# design.net
KiCad netlist of a schematic drawn in Altium Designer
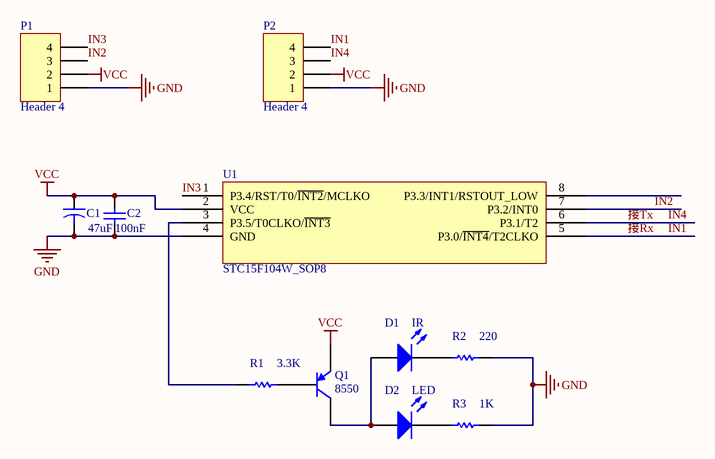
[diagram p0: 红外发射.SchDoc]

(export (version "E")
  (design (tool "Eeschema 10.0.6"))
  (components
    (comp (ref "C1")
      (value "47uF")
      (footprint "C1210_L")
      (description "Capacitor")
      (fields (field (name "Comment") "Cap2") (field (name "PUBLISHER") "Altium Limited"))
      (libsource (lib "Miscellaneous Devices") (part "Cap2"))
    )
    (comp (ref "C2")
      (value "100nF")
      (footprint "6-0805_N")
      (description "Capacitor")
      (fields (field (name "Comment") "Cap") (field (name "PUBLISHER") "Altium Limited"))
      (libsource (lib "Miscellaneous Devices") (part "Cap"))
    )
    (comp (ref "D1")
      (value "IR")
      (footprint "PIN2")
      (description "Typical INFRARED GaAs LED")
      (fields (field (name "PUBLISHER") "Altium Limited"))
      (libsource (lib "Miscellaneous Devices") (part "LED0"))
    )
    (comp (ref "D2")
      (value "LED")
      (footprint "6-0805_N")
      (description "Typical INFRARED GaAs LED")
      (fields (field (name "PUBLISHER") "Altium Limited"))
      (libsource (lib "Miscellaneous Devices") (part "LED0"))
    )
    (comp (ref "P1")
      (value "Header 4")
      (footprint "HDR1X4")
      (description "Header, 4-Pin")
      (fields (field (name "PUBLISHER") "Altium Limited"))
      (libsource (lib "Miscellaneous Connectors") (part "Header 4"))
    )
    (comp (ref "P2")
      (value "Header 4")
      (footprint "HDR1X4")
      (description "Header, 4-Pin")
      (fields (field (name "PUBLISHER") "Altium Limited"))
      (libsource (lib "Miscellaneous Connectors") (part "Header 4"))
    )
    (comp (ref "Q1")
      (value "8550")
      (footprint "SOT-23_N")
      (description "PNP General Purpose Amplifier")
      (fields (field (name "PUBLISHER") "Altium Limited"))
      (libsource (lib "Miscellaneous Devices") (part "2N3906"))
    )
    (comp (ref "R1")
      (value "3.3K")
      (footprint "6-0805_N")
      (description "Resistor")
      (fields (field (name "Comment") "Res1") (field (name "PUBLISHER") "Altium Limited"))
      (libsource (lib "Miscellaneous Devices") (part "Res1"))
    )
    (comp (ref "R2")
      (value "220")
      (footprint "6-0805_N")
      (description "Resistor")
      (fields (field (name "Comment") "Res1") (field (name "PUBLISHER") "Altium Limited"))
      (libsource (lib "Miscellaneous Devices") (part "Res1"))
    )
    (comp (ref "R3")
      (value "1K")
      (footprint "6-0805_N")
      (description "Resistor")
      (fields (field (name "Comment") "Res1") (field (name "PUBLISHER") "Altium Limited"))
      (libsource (lib "Miscellaneous Devices") (part "Res1"))
    )
    (comp (ref "U1")
      (value "STC15F104W_SOP8")
      (footprint "DFN8")
      (libsource (lib "stcmcu_altium_lib") (part "STC15F101W_SOP8_DIP8"))
    )
  )
  (nets
    (net (code "1") (name "/IN1") (class "Default")
      (node (ref "P2") (pin "4") (pinfunction "4_4") (pintype "passive"))
      (node (ref "U1") (pin "5") (pinfunction "P3.0/~{INT4}/T2CLKO_5") (pintype "passive"))
    )
    (net (code "2") (name "/IN2") (class "Default")
      (node (ref "P1") (pin "3") (pinfunction "3_3") (pintype "passive"))
      (node (ref "U1") (pin "7") (pinfunction "P3.2/INT0_7") (pintype "passive"))
    )
    (net (code "3") (name "/IN3") (class "Default")
      (node (ref "P1") (pin "4") (pinfunction "4_4") (pintype "passive"))
      (node (ref "U1") (pin "1") (pinfunction "P3.4/RST/T0/~{INT2}/MCLKO_1") (pintype "passive"))
    )
    (net (code "4") (name "/IN4") (class "Default")
      (node (ref "P2") (pin "3") (pinfunction "3_3") (pintype "passive"))
      (node (ref "U1") (pin "6") (pinfunction "P3.1/T2_6") (pintype "passive"))
    )
    (net (code "5") (name "GND") (class "Default")
      (node (ref "C1") (pin "2") (pinfunction "2_2") (pintype "passive"))
      (node (ref "C2") (pin "1") (pinfunction "1_1") (pintype "passive"))
      (node (ref "P1") (pin "1") (pinfunction "1_1") (pintype "passive"))
      (node (ref "P2") (pin "1") (pinfunction "1_1") (pintype "passive"))
      (node (ref "R2") (pin "2") (pinfunction "2_2") (pintype "passive"))
      (node (ref "R3") (pin "2") (pinfunction "2_2") (pintype "passive"))
      (node (ref "U1") (pin "4") (pinfunction "GND_4") (pintype "passive"))
    )
    (net (code "6") (name "Net-(D1-A)") (class "Default")
      (node (ref "D1") (pin "1") (pinfunction "A_1") (pintype "passive"))
      (node (ref "D2") (pin "1") (pinfunction "A_1") (pintype "passive"))
      (node (ref "Q1") (pin "3") (pinfunction "C_3") (pintype "passive"))
    )
    (net (code "7") (name "Net-(D1-K)") (class "Default")
      (node (ref "D1") (pin "2") (pinfunction "K_2") (pintype "passive"))
      (node (ref "R2") (pin "1") (pinfunction "1_1") (pintype "passive"))
    )
    (net (code "8") (name "Net-(D2-K)") (class "Default")
      (node (ref "D2") (pin "2") (pinfunction "K_2") (pintype "passive"))
      (node (ref "R3") (pin "1") (pinfunction "1_1") (pintype "passive"))
    )
    (net (code "9") (name "Net-(Q1-B)") (class "Default")
      (node (ref "Q1") (pin "2") (pinfunction "B_2") (pintype "passive"))
      (node (ref "R1") (pin "2") (pinfunction "2_2") (pintype "passive"))
    )
    (net (code "10") (name "Net-(U1-P3.5{slash}T0CLKO{slash}~{INT3})") (class "Default")
      (node (ref "R1") (pin "1") (pinfunction "1_1") (pintype "passive"))
      (node (ref "U1") (pin "3") (pinfunction "P3.5/T0CLKO/~{INT3}_3") (pintype "passive"))
    )
    (net (code "11") (name "VCC") (class "Default")
      (node (ref "C1") (pin "1") (pinfunction "1_1") (pintype "passive"))
      (node (ref "C2") (pin "2") (pinfunction "2_2") (pintype "passive"))
      (node (ref "P1") (pin "2") (pinfunction "2_2") (pintype "passive"))
      (node (ref "P2") (pin "2") (pinfunction "2_2") (pintype "passive"))
      (node (ref "Q1") (pin "1") (pinfunction "E_1") (pintype "passive"))
      (node (ref "U1") (pin "2") (pinfunction "VCC_2") (pintype "passive"))
    )
    (net (code "12") (name "unconnected-(U1-P3.3{slash}INT1{slash}RSTOUT_LOW-Pad8)") (class "Default")
      (node (ref "U1") (pin "8") (pinfunction "P3.3/INT1/RSTOUT_LOW_8") (pintype "passive"))
    )
  )
)
